# FPGA_microSD.net
KiCad netlist of a schematic drawn in Altium Designer
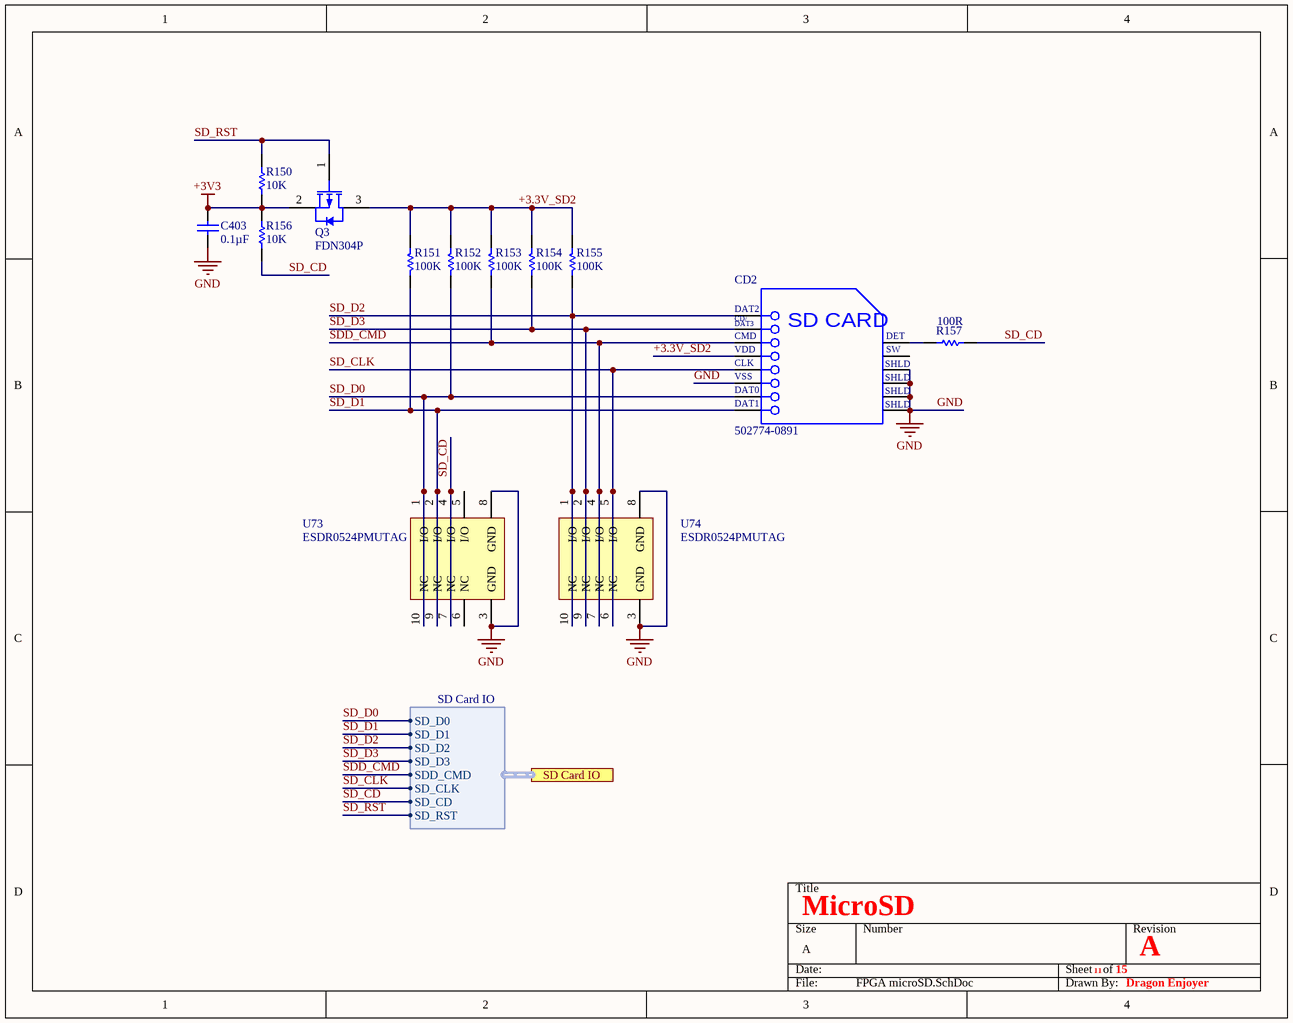
[diagram p0: FPGA microSD.SchDoc]

(export (version "E")
  (design (tool "Eeschema 10.0.6"))
  (components
    (comp (ref "C403")
      (value "CC0402ZRY5V8BB104")
      (footprint "CAPC1005X55X25LL05T05")
      (description "Chip Capacitor, 100 nF, -20% to 80%, 25 V, -30 to 85 degC, 0402 (1005 Metric), RoHS, Tape and Reel")
      (fields
        (field (name "TOLERANCE") "-20%,+80%")
        (field (name "CAPACITANCE") "0.1µF")
        (field (name "MANUFACTURER") "Yageo")
      )
      (libsource (lib "Altium Content Vault") (part "CAP-NP-2"))
    )
    (comp (ref "CD2")
      (value "502774-0891")
      (footprint "MOLX-502774-0891_V")
      (description "Micro SD Memory Card Connector, 0.5 A, 10 V (DC), -25 to 85 degC, 8-Pin SMT, RoHS, Tape and Reel")
      (fields (field (name "MANUFACTURER") "Molex"))
      (libsource (lib "Altium Content Vault") (part "CN-SD-8-2SW-4S_B"))
    )
    (comp (ref "Q3")
      (value "FDN304P")
      (footprint "FAIR-SSOT3L-3_V")
      (fields (field (name "MANUFACTURER") "Fairchild Semiconductor"))
      (libsource (lib "Altium Content Vault") (part "PEMOS-GSD-3"))
    )
    (comp (ref "R150")
      (value "10K")
      (footprint "RESC1609X50X30NL8T20")
      (description "Chip Resistor, 10 KOhm, +/- 1%, 100 mW, -55 to 155 degC, 0603 (1608 Metric), RoHS, Tape and Reel")
      (fields (field (name "MANUFACTURER") "Vishay Semiconductor"))
      (libsource (lib "Altium Content Vault") (part "RES-2"))
    )
    (comp (ref "R151")
      (value "100K")
      (footprint "RESC1005X40X25LL05T05")
      (fields (field (name "PART NUMBER") "CRCW0402100KJNED") (field (name "MANUFACTURER") "Vishay Dale"))
      (libsource (lib "Altium Content Vault") (part "RES"))
    )
    (comp (ref "R152")
      (value "100K")
      (footprint "RESC1005X40X25LL05T05")
      (fields (field (name "PART NUMBER") "CRCW0402100KJNED") (field (name "MANUFACTURER") "Vishay Dale"))
      (libsource (lib "Altium Content Vault") (part "RES"))
    )
    (comp (ref "R153")
      (value "100K")
      (footprint "RESC1005X40X25LL05T05")
      (fields (field (name "PART NUMBER") "CRCW0402100KJNED") (field (name "MANUFACTURER") "Vishay Dale"))
      (libsource (lib "Altium Content Vault") (part "RES"))
    )
    (comp (ref "R154")
      (value "100K")
      (footprint "RESC1005X40X25LL05T05")
      (fields (field (name "PART NUMBER") "CRCW0402100KJNED") (field (name "MANUFACTURER") "Vishay Dale"))
      (libsource (lib "Altium Content Vault") (part "RES"))
    )
    (comp (ref "R155")
      (value "100K")
      (footprint "RESC1005X40X25LL05T05")
      (fields (field (name "PART NUMBER") "CRCW0402100KJNED") (field (name "MANUFACTURER") "Vishay Dale"))
      (libsource (lib "Altium Content Vault") (part "RES"))
    )
    (comp (ref "R156")
      (value "10K")
      (footprint "RESC1609X50X30NL8T20")
      (description "Chip Resistor, 10 KOhm, +/- 1%, 100 mW, -55 to 155 degC, 0603 (1608 Metric), RoHS, Tape and Reel")
      (fields (field (name "MANUFACTURER") "Vishay Semiconductor"))
      (libsource (lib "Altium Content Vault") (part "RES-2"))
    )
    (comp (ref "R157")
      (value "100R")
      (footprint "RESC1005X40X25ML05T10")
      (fields (field (name "PART NUMBER") "RC0402FR-07100RL") (field (name "MANUFACTURER") "Yageo / Phycomp"))
      (libsource (lib "Altium Content Vault") (part "RES"))
    )
    (comp (ref "U73")
      (value "ESDR0524PMUTAG")
      (footprint "ONSC-UDFN-10-517BB-01_V")
      (fields (field (name "MANUFACTURER") "On Semiconductor"))
      (libsource (lib "Altium Content Vault") (part "ONSC-ESDXXXXXX-UDFN-10-517BB-01"))
    )
    (comp (ref "U74")
      (value "ESDR0524PMUTAG")
      (footprint "ONSC-UDFN-10-517BB-01_V")
      (fields (field (name "MANUFACTURER") "On Semiconductor"))
      (libsource (lib "Altium Content Vault") (part "ONSC-ESDXXXXXX-UDFN-10-517BB-01"))
    )
  )
  (nets
    (net (code "4") (name "+3V3") (class "Default")
      (node (ref "C403") (pin "2") (pinfunction "2_2") (pintype "passive"))
      (node (ref "Q3") (pin "2") (pinfunction "SOURCE_2") (pintype "passive"))
      (node (ref "R150") (pin "1") (pinfunction "1_1") (pintype "passive"))
      (node (ref "R156") (pin "2") (pinfunction "2_2") (pintype "passive"))
    )
    (net (code "5") (name "/+3.3V_SD2") (class "Default")
      (node (ref "CD2") (pin "4") (pinfunction "VDD_4") (pintype "passive"))
      (node (ref "Q3") (pin "3") (pinfunction "DRAIN_3") (pintype "passive"))
      (node (ref "R151") (pin "1") (pinfunction "1_1") (pintype "passive"))
      (node (ref "R152") (pin "1") (pinfunction "1_1") (pintype "passive"))
      (node (ref "R153") (pin "1") (pinfunction "1_1") (pintype "passive"))
      (node (ref "R154") (pin "1") (pinfunction "1_1") (pintype "passive"))
      (node (ref "R155") (pin "1") (pinfunction "1_1") (pintype "passive"))
    )
    (net (code "6") (name "/SDD_CMD") (class "Default")
      (node (ref "CD2") (pin "3") (pinfunction "CMD_3") (pintype "passive"))
      (node (ref "R153") (pin "2") (pinfunction "2_2") (pintype "passive"))
      (node (ref "U74") (pin "4") (pinfunction "I/O_4") (pintype "passive"))
      (node (ref "U74") (pin "7") (pinfunction "NC_7") (pintype "passive"))
    )
    (net (code "7") (name "/SD_CD") (class "Default")
      (node (ref "R156") (pin "1") (pinfunction "1_1") (pintype "passive"))
      (node (ref "R157") (pin "2") (pinfunction "2_2") (pintype "passive"))
      (node (ref "U73") (pin "4") (pinfunction "I/O_4") (pintype "passive"))
      (node (ref "U73") (pin "7") (pinfunction "NC_7") (pintype "passive"))
    )
    (net (code "8") (name "/SD_CLK") (class "Default")
      (node (ref "CD2") (pin "5") (pinfunction "CLK_5") (pintype "passive"))
      (node (ref "U74") (pin "5") (pinfunction "I/O_5") (pintype "passive"))
      (node (ref "U74") (pin "6") (pinfunction "NC_6") (pintype "passive"))
    )
    (net (code "9") (name "/SD_D0") (class "Default")
      (node (ref "CD2") (pin "7") (pinfunction "DAT0_7") (pintype "passive"))
      (node (ref "R152") (pin "2") (pinfunction "2_2") (pintype "passive"))
      (node (ref "U73") (pin "1") (pinfunction "I/O_1") (pintype "passive"))
      (node (ref "U73") (pin "10") (pinfunction "NC_10") (pintype "passive"))
    )
    (net (code "10") (name "/SD_D1") (class "Default")
      (node (ref "CD2") (pin "8") (pinfunction "DAT1_8") (pintype "passive"))
      (node (ref "R151") (pin "2") (pinfunction "2_2") (pintype "passive"))
      (node (ref "U73") (pin "2") (pinfunction "I/O_2") (pintype "passive"))
      (node (ref "U73") (pin "9") (pinfunction "NC_9") (pintype "passive"))
    )
    (net (code "11") (name "/SD_D2") (class "Default")
      (node (ref "CD2") (pin "1") (pinfunction "DAT2_1") (pintype "passive"))
      (node (ref "R155") (pin "2") (pinfunction "2_2") (pintype "passive"))
      (node (ref "U74") (pin "1") (pinfunction "I/O_1") (pintype "passive"))
      (node (ref "U74") (pin "10") (pinfunction "NC_10") (pintype "passive"))
    )
    (net (code "12") (name "/SD_D3") (class "Default")
      (node (ref "CD2") (pin "2") (pinfunction "CD/DAT3_2") (pintype "passive"))
      (node (ref "R154") (pin "2") (pinfunction "2_2") (pintype "passive"))
      (node (ref "U74") (pin "2") (pinfunction "I/O_2") (pintype "passive"))
      (node (ref "U74") (pin "9") (pinfunction "NC_9") (pintype "passive"))
    )
    (net (code "13") (name "/SD_RST") (class "Default")
      (node (ref "Q3") (pin "1") (pinfunction "GATE_1") (pintype "passive"))
      (node (ref "R150") (pin "2") (pinfunction "2_2") (pintype "passive"))
    )
    (net (code "15") (name "GND") (class "Default")
      (node (ref "C403") (pin "1") (pinfunction "1_1") (pintype "passive"))
      (node (ref "CD2") (pin "11") (pinfunction "SHLD_11") (pintype "passive"))
      (node (ref "CD2") (pin "12") (pinfunction "SHLD_12") (pintype "passive"))
      (node (ref "CD2") (pin "13") (pinfunction "SHLD_13") (pintype "passive"))
      (node (ref "CD2") (pin "14") (pinfunction "SHLD_14") (pintype "passive"))
      (node (ref "CD2") (pin "6") (pinfunction "VSS_6") (pintype "passive"))
      (node (ref "U73") (pin "3") (pinfunction "GND_3") (pintype "passive"))
      (node (ref "U73") (pin "8") (pinfunction "GND_8") (pintype "passive"))
      (node (ref "U74") (pin "3") (pinfunction "GND_3") (pintype "passive"))
      (node (ref "U74") (pin "8") (pinfunction "GND_8") (pintype "passive"))
    )
    (net (code "16") (name "Net-(CD2-DETECT)") (class "Default")
      (node (ref "CD2") (pin "9") (pinfunction "DETECT_9") (pintype "passive"))
      (node (ref "R157") (pin "1") (pinfunction "1_1") (pintype "passive"))
    )
    (net (code "17") (name "unconnected-(CD2-SWITCH-Pad10)") (class "Default")
      (node (ref "CD2") (pin "10") (pinfunction "SWITCH_10") (pintype "passive"))
    )
    (net (code "18") (name "unconnected-(U73-I{slash}O-Pad5)") (class "Default")
      (node (ref "U73") (pin "5") (pinfunction "I/O_5") (pintype "passive"))
    )
    (net (code "19") (name "unconnected-(U73-NC-Pad6)") (class "Default")
      (node (ref "U73") (pin "6") (pinfunction "NC_6") (pintype "passive"))
    )
  )
)
